# boiler25.net
KiCad netlist of a schematic drawn in EAGLE
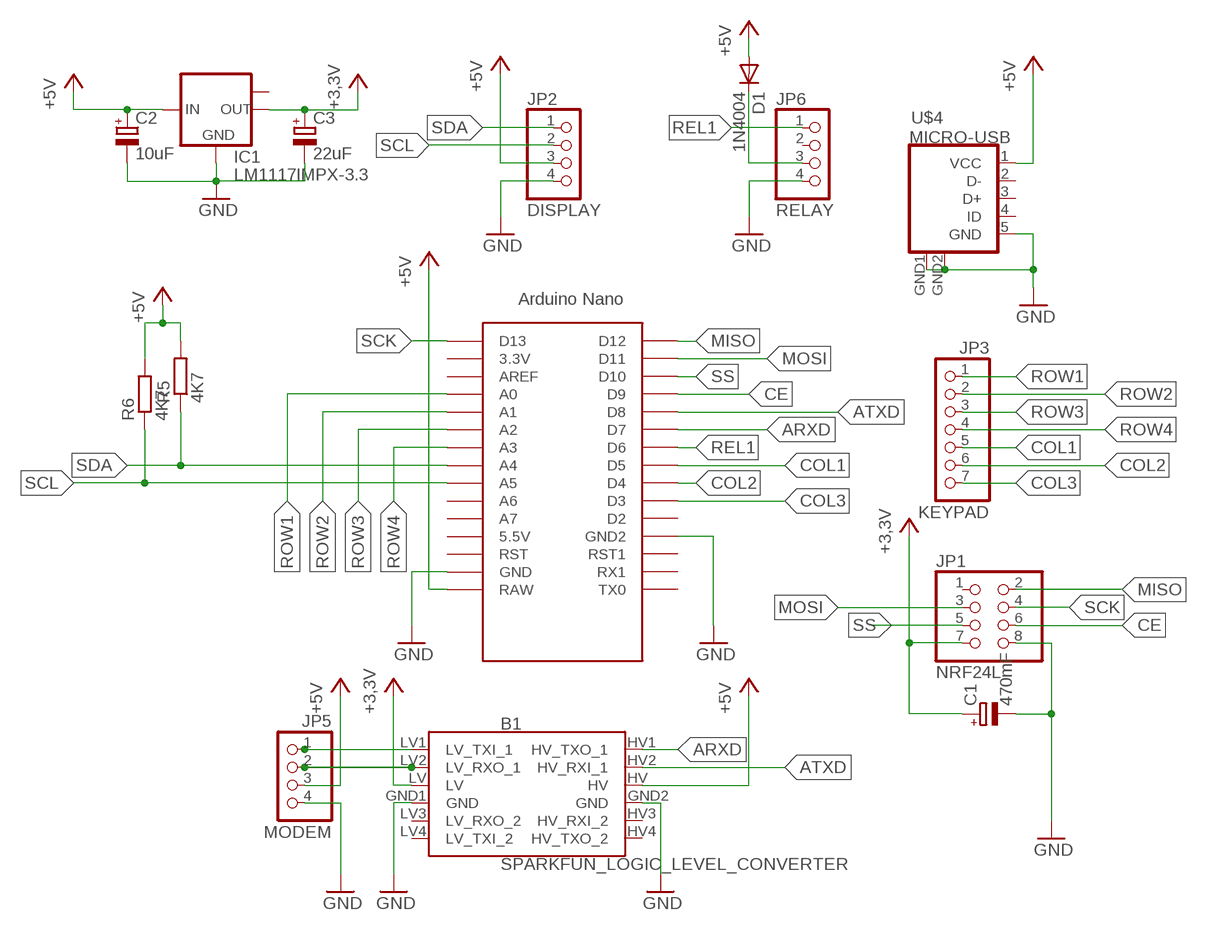
[diagram p0: schematic, sheet 1]

(export (version "E")
  (design (tool "Eeschema 10.0.6"))
  (components
    (comp (ref "B1")
      (value "SPARKFUN_LOGIC_LEVEL_CONVERTER")
      (footprint "eagle-import:SPARKFUN_LOGIC_LEVEL_CONVERTER")
      (libsource (lib "eagle-import") (part "SPARKFUN_LOGIC_LEVEL_CONVERTER"))
    )
    (comp (ref "C1")
      (value "470mF")
      (footprint "eagle-import:E3,5-8")
      (libsource (lib "eagle-import") (part "CPOL-EUE3.5-8"))
    )
    (comp (ref "C2")
      (value "10uF")
      (footprint "eagle-import:E1,8-4")
      (libsource (lib "eagle-import") (part "CPOL-EUE1.8-4"))
    )
    (comp (ref "C3")
      (value "22uF")
      (footprint "eagle-import:E1,8-4")
      (libsource (lib "eagle-import") (part "CPOL-EUE1.8-4"))
    )
    (comp (ref "D1")
      (value "1N4004")
      (footprint "eagle-import:DO41-10")
      (libsource (lib "eagle-import") (part "1N4004"))
    )
    (comp (ref "IC1")
      (value "LM1117IMPX-3.3")
      (footprint "eagle-import:SOT223")
      (libsource (lib "eagle-import") (part "LM1117IMPX-3.3"))
    )
    (comp (ref "JP1")
      (value "NRF24L")
      (footprint "eagle-import:2X04")
      (libsource (lib "eagle-import") (part "PINHD-2X4"))
    )
    (comp (ref "JP2")
      (value "DISPLAY")
      (footprint "eagle-import:1X04")
      (libsource (lib "eagle-import") (part "PINHD-1X4"))
    )
    (comp (ref "JP3")
      (value "KEYPAD")
      (footprint "eagle-import:1X07")
      (libsource (lib "eagle-import") (part "PINHD-1X7"))
    )
    (comp (ref "JP5")
      (value "MODEM")
      (footprint "eagle-import:1X04")
      (libsource (lib "eagle-import") (part "PINHD-1X4"))
    )
    (comp (ref "JP6")
      (value "RELAY")
      (footprint "eagle-import:1X04")
      (libsource (lib "eagle-import") (part "PINHD-1X4"))
    )
    (comp (ref "R5")
      (value "4K7")
      (footprint "eagle-import:M1206")
      (libsource (lib "eagle-import") (part "R-EU_M1206"))
    )
    (comp (ref "R6")
      (value "4K7")
      (footprint "eagle-import:M1206")
      (libsource (lib "eagle-import") (part "R-EU_M1206"))
    )
    (comp (ref "U$4")
      (value "MICRO-USB")
      (footprint "eagle-import:MICRO-USB")
      (libsource (lib "eagle-import") (part "MICRO-USB"))
    )
    (comp (ref "U$5")
      (value "NANO")
      (footprint "eagle-import:NANO")
      (libsource (lib "eagle-import") (part "NANO"))
    )
  )
  (nets
    (net (code "1") (name "+3,3V") (class "Default")
      (node (ref "B1") (pin "LV") (pinfunction "LV_LV") (pintype "power_in"))
      (node (ref "C1") (pin "+") (pinfunction "+_+") (pintype "passive"))
      (node (ref "C3") (pin "+") (pinfunction "+_+") (pintype "passive"))
      (node (ref "IC1") (pin "2") (pinfunction "OUT_2") (pintype "passive"))
      (node (ref "JP1") (pin "7") (pinfunction "7_7") (pintype "passive"))
    )
    (net (code "2") (name "+5V") (class "Default")
      (node (ref "B1") (pin "HV") (pinfunction "HV_HV") (pintype "power_in"))
      (node (ref "C2") (pin "+") (pinfunction "+_+") (pintype "passive"))
      (node (ref "D1") (pin "A") (pinfunction "A_A") (pintype "passive"))
      (node (ref "IC1") (pin "3") (pinfunction "IN_3") (pintype "input"))
      (node (ref "JP2") (pin "3") (pinfunction "3_3") (pintype "passive"))
      (node (ref "JP5") (pin "3") (pinfunction "3_3") (pintype "passive"))
      (node (ref "R5") (pin "2") (pinfunction "2_2") (pintype "passive"))
      (node (ref "R6") (pin "2") (pinfunction "2_2") (pintype "passive"))
      (node (ref "U$4") (pin "1") (pinfunction "VCC_1") (pintype "power_in"))
      (node (ref "U$5") (pin "RAW") (pinfunction "RAW_RAW") (pintype "bidirectional"))
    )
    (net (code "3") (name "ARXD") (class "Default")
      (node (ref "B1") (pin "HV1") (pinfunction "HV_TXO_1_HV1") (pintype "bidirectional"))
      (node (ref "U$5") (pin "D7") (pinfunction "D7_D7") (pintype "bidirectional"))
    )
    (net (code "4") (name "ATXD") (class "Default")
      (node (ref "B1") (pin "HV2") (pinfunction "HV_RXI_1_HV2") (pintype "bidirectional"))
      (node (ref "U$5") (pin "D8") (pinfunction "D8_D8") (pintype "bidirectional"))
    )
    (net (code "5") (name "CE") (class "Default")
      (node (ref "JP1") (pin "6") (pinfunction "6_6") (pintype "passive"))
      (node (ref "U$5") (pin "D9") (pinfunction "D9_D9") (pintype "bidirectional"))
    )
    (net (code "6") (name "COL1") (class "Default")
      (node (ref "JP3") (pin "5") (pinfunction "5_5") (pintype "passive"))
      (node (ref "U$5") (pin "D5") (pinfunction "D5_D5") (pintype "bidirectional"))
    )
    (net (code "7") (name "COL2") (class "Default")
      (node (ref "JP3") (pin "6") (pinfunction "6_6") (pintype "passive"))
      (node (ref "U$5") (pin "D4") (pinfunction "D4_D4") (pintype "bidirectional"))
    )
    (net (code "8") (name "COL3") (class "Default")
      (node (ref "JP3") (pin "7") (pinfunction "7_7") (pintype "passive"))
      (node (ref "U$5") (pin "D3") (pinfunction "D3_D3") (pintype "bidirectional"))
    )
    (net (code "9") (name "GND") (class "Default")
      (node (ref "B1") (pin "GND1") (pinfunction "GND_GND1") (pintype "power_in"))
      (node (ref "B1") (pin "GND2") (pinfunction "GND_GND2") (pintype "power_in"))
      (node (ref "C1") (pin "-") (pinfunction "-_-") (pintype "passive"))
      (node (ref "C2") (pin "-") (pinfunction "-_-") (pintype "passive"))
      (node (ref "C3") (pin "-") (pinfunction "-_-") (pintype "passive"))
      (node (ref "IC1") (pin "1") (pinfunction "GND_1") (pintype "input"))
      (node (ref "JP1") (pin "8") (pinfunction "8_8") (pintype "passive"))
      (node (ref "JP2") (pin "4") (pinfunction "4_4") (pintype "passive"))
      (node (ref "JP5") (pin "4") (pinfunction "4_4") (pintype "passive"))
      (node (ref "JP6") (pin "4") (pinfunction "4_4") (pintype "passive"))
      (node (ref "U$4") (pin "5") (pinfunction "GND_5") (pintype "power_in"))
      (node (ref "U$4") (pin "GND1") (pinfunction "GND_GND1") (pintype "power_in"))
      (node (ref "U$4") (pin "GND2") (pinfunction "GND_GND2") (pintype "power_in"))
      (node (ref "U$5") (pin "GND") (pinfunction "GND_GND") (pintype "bidirectional"))
      (node (ref "U$5") (pin "GND1") (pinfunction "GND2_GND1") (pintype "bidirectional"))
    )
    (net (code "10") (name "MISO") (class "Default")
      (node (ref "JP1") (pin "2") (pinfunction "2_2") (pintype "passive"))
      (node (ref "U$5") (pin "D12") (pinfunction "D12_D12") (pintype "bidirectional"))
    )
    (net (code "11") (name "MOSI") (class "Default")
      (node (ref "JP1") (pin "3") (pinfunction "3_3") (pintype "passive"))
      (node (ref "U$5") (pin "D11") (pinfunction "D11_D11") (pintype "bidirectional"))
    )
    (net (code "12") (name "Net-(B1-LV_RXO_1)") (class "Default")
      (node (ref "B1") (pin "LV2") (pinfunction "LV_RXO_1_LV2") (pintype "bidirectional"))
      (node (ref "JP5") (pin "2") (pinfunction "2_2") (pintype "passive"))
    )
    (net (code "13") (name "Net-(B1-LV_TXI_1)") (class "Default")
      (node (ref "B1") (pin "LV1") (pinfunction "LV_TXI_1_LV1") (pintype "bidirectional"))
      (node (ref "JP5") (pin "1") (pinfunction "1_1") (pintype "passive"))
    )
    (net (code "14") (name "Net-(D1-PadC)") (class "Default")
      (node (ref "D1") (pin "C") (pinfunction "C_C") (pintype "passive"))
      (node (ref "JP6") (pin "3") (pinfunction "3_3") (pintype "passive"))
    )
    (net (code "15") (name "REL1") (class "Default")
      (node (ref "JP6") (pin "1") (pinfunction "1_1") (pintype "passive"))
      (node (ref "U$5") (pin "D6") (pinfunction "D6_D6") (pintype "bidirectional"))
    )
    (net (code "16") (name "ROW1") (class "Default")
      (node (ref "JP3") (pin "1") (pinfunction "1_1") (pintype "passive"))
      (node (ref "U$5") (pin "A0") (pinfunction "A0_A0") (pintype "bidirectional"))
    )
    (net (code "17") (name "ROW2") (class "Default")
      (node (ref "JP3") (pin "2") (pinfunction "2_2") (pintype "passive"))
      (node (ref "U$5") (pin "A1") (pinfunction "A1_A1") (pintype "bidirectional"))
    )
    (net (code "18") (name "ROW3") (class "Default")
      (node (ref "JP3") (pin "3") (pinfunction "3_3") (pintype "passive"))
      (node (ref "U$5") (pin "A2") (pinfunction "A2_A2") (pintype "bidirectional"))
    )
    (net (code "19") (name "ROW4") (class "Default")
      (node (ref "JP3") (pin "4") (pinfunction "4_4") (pintype "passive"))
      (node (ref "U$5") (pin "A3") (pinfunction "A3_A3") (pintype "bidirectional"))
    )
    (net (code "20") (name "SCK") (class "Default")
      (node (ref "JP1") (pin "4") (pinfunction "4_4") (pintype "passive"))
      (node (ref "U$5") (pin "D13") (pinfunction "D13_D13") (pintype "bidirectional"))
    )
    (net (code "21") (name "SCL") (class "Default")
      (node (ref "JP2") (pin "2") (pinfunction "2_2") (pintype "passive"))
      (node (ref "R6") (pin "1") (pinfunction "1_1") (pintype "passive"))
      (node (ref "U$5") (pin "A5") (pinfunction "A5_A5") (pintype "bidirectional"))
    )
    (net (code "22") (name "SDA") (class "Default")
      (node (ref "JP2") (pin "1") (pinfunction "1_1") (pintype "passive"))
      (node (ref "R5") (pin "1") (pinfunction "1_1") (pintype "passive"))
      (node (ref "U$5") (pin "A4") (pinfunction "A4_A4") (pintype "bidirectional"))
    )
    (net (code "23") (name "SS") (class "Default")
      (node (ref "JP1") (pin "5") (pinfunction "5_5") (pintype "passive"))
      (node (ref "U$5") (pin "D10") (pinfunction "D10_D10") (pintype "bidirectional"))
    )
    (net (code "24") (name "unconnected-(B1-HV_RXI_2-PadHV3)") (class "Default")
      (node (ref "B1") (pin "HV3") (pinfunction "HV_RXI_2_HV3") (pintype "bidirectional"))
    )
    (net (code "25") (name "unconnected-(B1-HV_TXO_2-PadHV4)") (class "Default")
      (node (ref "B1") (pin "HV4") (pinfunction "HV_TXO_2_HV4") (pintype "bidirectional"))
    )
    (net (code "26") (name "unconnected-(B1-LV_RXO_2-PadLV3)") (class "Default")
      (node (ref "B1") (pin "LV3") (pinfunction "LV_RXO_2_LV3") (pintype "bidirectional"))
    )
    (net (code "27") (name "unconnected-(B1-LV_TXI_2-PadLV4)") (class "Default")
      (node (ref "B1") (pin "LV4") (pinfunction "LV_TXI_2_LV4") (pintype "bidirectional"))
    )
    (net (code "28") (name "unconnected-(IC1-OUT1-PadTAB)") (class "Default")
      (node (ref "IC1") (pin "TAB") (pinfunction "OUT1_TAB") (pintype "passive"))
    )
    (net (code "29") (name "unconnected-(JP1-Pad1)") (class "Default")
      (node (ref "JP1") (pin "1") (pinfunction "1_1") (pintype "passive"))
    )
    (net (code "30") (name "unconnected-(JP6-Pad2)") (class "Default")
      (node (ref "JP6") (pin "2") (pinfunction "2_2") (pintype "passive"))
    )
    (net (code "31") (name "unconnected-(U$4-D+-Pad3)") (class "Default")
      (node (ref "U$4") (pin "3") (pinfunction "D+_3") (pintype "bidirectional"))
    )
    (net (code "32") (name "unconnected-(U$4-D--Pad2)") (class "Default")
      (node (ref "U$4") (pin "2") (pinfunction "D-_2") (pintype "bidirectional"))
    )
    (net (code "33") (name "unconnected-(U$4-ID-Pad4)") (class "Default")
      (node (ref "U$4") (pin "4") (pinfunction "ID_4") (pintype "bidirectional"))
    )
    (net (code "34") (name "unconnected-(U$5-5.5V-Pad5V)") (class "Default")
      (node (ref "U$5") (pin "5V") (pinfunction "5.5V_5V") (pintype "bidirectional"))
    )
    (net (code "35") (name "unconnected-(U$5-Pad3.3V)") (class "Default")
      (node (ref "U$5") (pin "3.3V") (pinfunction "3.3V_3.3V") (pintype "bidirectional"))
    )
    (net (code "36") (name "unconnected-(U$5-PadA6)") (class "Default")
      (node (ref "U$5") (pin "A6") (pinfunction "A6_A6") (pintype "bidirectional"))
    )
    (net (code "37") (name "unconnected-(U$5-PadA7)") (class "Default")
      (node (ref "U$5") (pin "A7") (pinfunction "A7_A7") (pintype "bidirectional"))
    )
    (net (code "38") (name "unconnected-(U$5-PadAREF)") (class "Default")
      (node (ref "U$5") (pin "AREF") (pinfunction "AREF_AREF") (pintype "bidirectional"))
    )
    (net (code "39") (name "unconnected-(U$5-PadD2)") (class "Default")
      (node (ref "U$5") (pin "D2") (pinfunction "D2_D2") (pintype "bidirectional"))
    )
    (net (code "40") (name "unconnected-(U$5-PadICSP1)") (class "Default")
      (node (ref "U$5") (pin "ICSP1") (pinfunction "ICSP1_ICSP1") (pintype "bidirectional"))
    )
    (net (code "41") (name "unconnected-(U$5-PadICSP2)") (class "Default")
      (node (ref "U$5") (pin "ICSP2") (pinfunction "ICSP2_ICSP2") (pintype "bidirectional"))
    )
    (net (code "42") (name "unconnected-(U$5-PadICSP3)") (class "Default")
      (node (ref "U$5") (pin "ICSP3") (pinfunction "ICSP3_ICSP3") (pintype "bidirectional"))
    )
    (net (code "43") (name "unconnected-(U$5-PadICSP4)") (class "Default")
      (node (ref "U$5") (pin "ICSP4") (pinfunction "ICSP4_ICSP4") (pintype "bidirectional"))
    )
    (net (code "44") (name "unconnected-(U$5-PadICSP5)") (class "Default")
      (node (ref "U$5") (pin "ICSP5") (pinfunction "ICSP5_ICSP5") (pintype "bidirectional"))
    )
    (net (code "45") (name "unconnected-(U$5-PadICSP6)") (class "Default")
      (node (ref "U$5") (pin "ICSP6") (pinfunction "ICSP6_ICSP6") (pintype "bidirectional"))
    )
    (net (code "46") (name "unconnected-(U$5-PadRST)") (class "Default")
      (node (ref "U$5") (pin "RST") (pinfunction "RST_RST") (pintype "bidirectional"))
    )
    (net (code "47") (name "unconnected-(U$5-PadRST1)") (class "Default")
      (node (ref "U$5") (pin "RST1") (pinfunction "RST1_RST1") (pintype "bidirectional"))
    )
    (net (code "48") (name "unconnected-(U$5-PadRX1)") (class "Default")
      (node (ref "U$5") (pin "RX1") (pinfunction "RX1_RX1") (pintype "bidirectional"))
    )
    (net (code "49") (name "unconnected-(U$5-PadTX0)") (class "Default")
      (node (ref "U$5") (pin "TX0") (pinfunction "TX0_TX0") (pintype "bidirectional"))
    )
  )
)
